# DigitalIO.net
KiCad netlist of a schematic drawn in Altium Designer
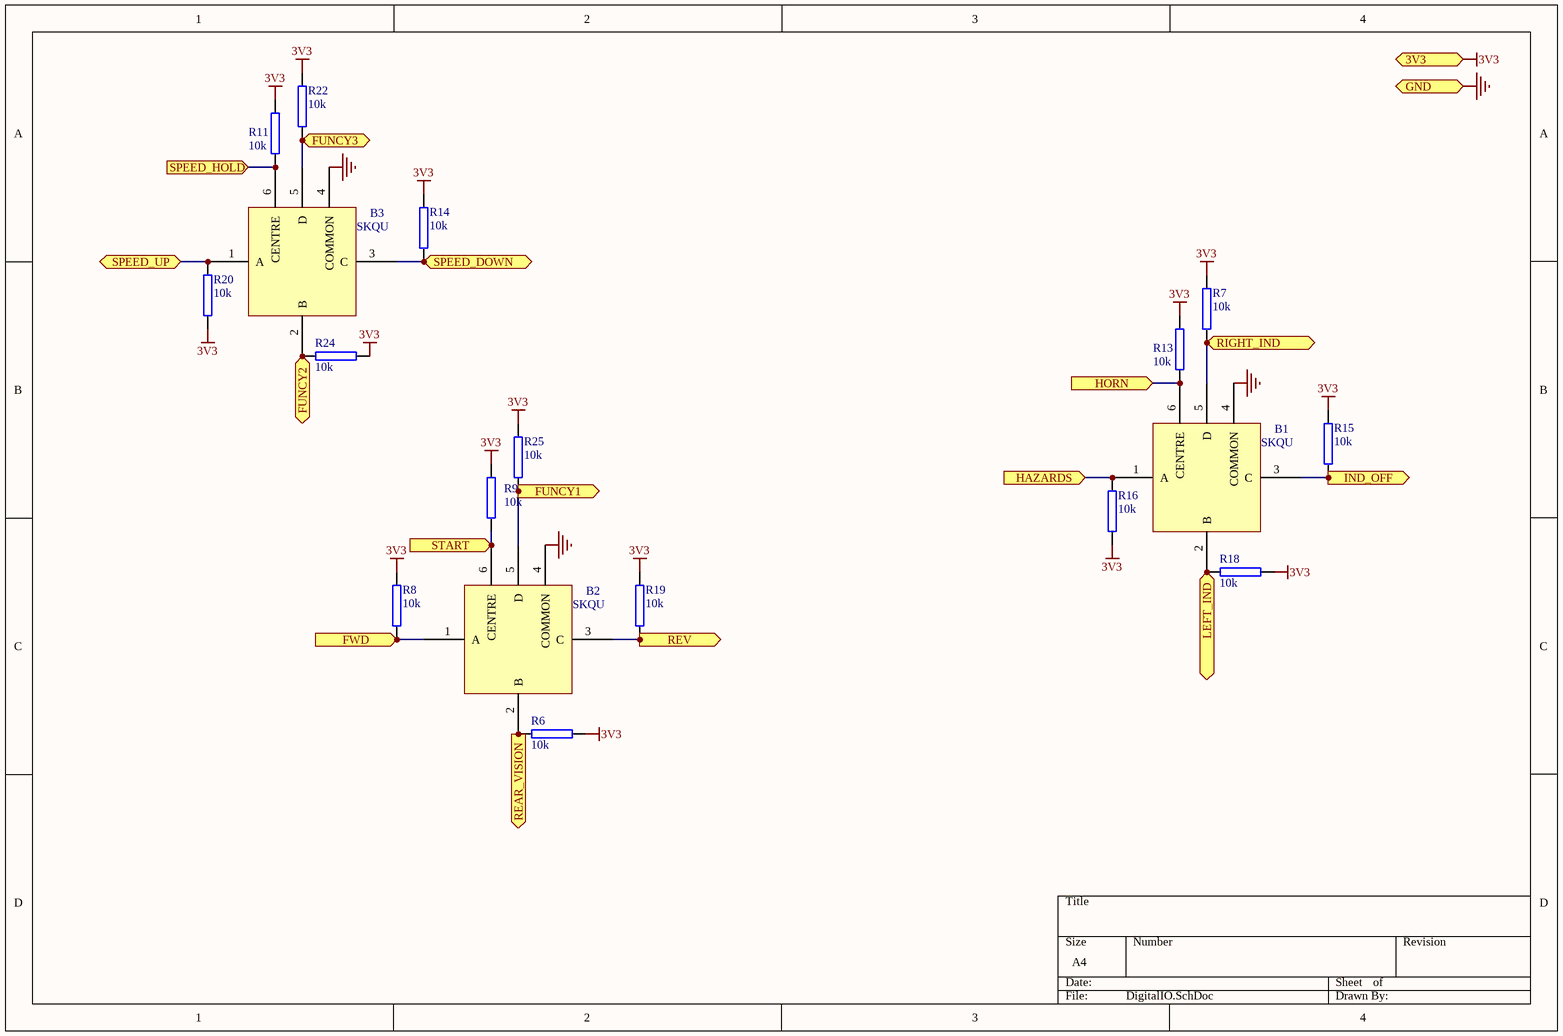
[diagram p0: DigitalIO.SchDoc]

(export (version "E")
  (design (tool "Eeschema 10.0.6"))
  (components
    (comp (ref "B1")
      (value "SKQU")
      (footprint "SKQU")
      (description "Multi-directional switch")
      (libsource (lib "Miscellaneous") (part "SKQU"))
    )
    (comp (ref "B2")
      (value "SKQU")
      (footprint "SKQU")
      (description "Multi-directional switch")
      (libsource (lib "Miscellaneous") (part "SKQU"))
    )
    (comp (ref "B3")
      (value "SKQU")
      (footprint "SKQU")
      (description "Multi-directional switch")
      (libsource (lib "Miscellaneous") (part "SKQU"))
    )
    (comp (ref "R6")
      (value "10k")
      (footprint "0603")
      (description "Standard Resistor")
      (libsource (lib "*") (part "RES"))
    )
    (comp (ref "R7")
      (value "10k")
      (footprint "0603")
      (description "Standard Resistor")
      (libsource (lib "*") (part "RES"))
    )
    (comp (ref "R8")
      (value "10k")
      (footprint "0603")
      (description "Standard Resistor")
      (libsource (lib "*") (part "RES"))
    )
    (comp (ref "R9")
      (value "10k")
      (footprint "0603")
      (description "Standard Resistor")
      (libsource (lib "*") (part "RES"))
    )
    (comp (ref "R11")
      (value "10k")
      (footprint "0603")
      (description "Standard Resistor")
      (libsource (lib "*") (part "RES"))
    )
    (comp (ref "R13")
      (value "10k")
      (footprint "0603")
      (description "Standard Resistor")
      (libsource (lib "*") (part "RES"))
    )
    (comp (ref "R14")
      (value "10k")
      (footprint "0603")
      (description "Standard Resistor")
      (libsource (lib "*") (part "RES"))
    )
    (comp (ref "R15")
      (value "10k")
      (footprint "0603")
      (description "Standard Resistor")
      (libsource (lib "*") (part "RES"))
    )
    (comp (ref "R16")
      (value "10k")
      (footprint "0603")
      (description "Standard Resistor")
      (libsource (lib "*") (part "RES"))
    )
    (comp (ref "R18")
      (value "10k")
      (footprint "0603")
      (description "Standard Resistor")
      (libsource (lib "*") (part "RES"))
    )
    (comp (ref "R19")
      (value "10k")
      (footprint "0603")
      (description "Standard Resistor")
      (libsource (lib "*") (part "RES"))
    )
    (comp (ref "R20")
      (value "10k")
      (footprint "0603")
      (description "Standard Resistor")
      (libsource (lib "*") (part "RES"))
    )
    (comp (ref "R22")
      (value "10k")
      (footprint "0603")
      (description "Standard Resistor")
      (libsource (lib "*") (part "RES"))
    )
    (comp (ref "R24")
      (value "10k")
      (footprint "0603")
      (description "Standard Resistor")
      (libsource (lib "*") (part "RES"))
    )
    (comp (ref "R25")
      (value "10k")
      (footprint "0603")
      (description "Standard Resistor")
      (libsource (lib "*") (part "RES"))
    )
  )
  (nets
    (net (code "1") (name "/FUNCY1") (class "Default")
      (node (ref "B2") (pin "5") (pinfunction "D_5") (pintype "passive"))
      (node (ref "R25") (pin "2") (pintype "passive"))
    )
    (net (code "2") (name "/FUNCY2") (class "Default")
      (node (ref "B3") (pin "2") (pinfunction "B_2") (pintype "passive"))
      (node (ref "R24") (pin "1") (pintype "passive"))
    )
    (net (code "3") (name "/FUNCY3") (class "Default")
      (node (ref "B3") (pin "5") (pinfunction "D_5") (pintype "passive"))
      (node (ref "R22") (pin "2") (pintype "passive"))
    )
    (net (code "4") (name "/FWD") (class "Default")
      (node (ref "B2") (pin "1") (pinfunction "A_1") (pintype "passive"))
      (node (ref "R8") (pin "1") (pintype "passive"))
    )
    (net (code "5") (name "/HAZARDS") (class "Default")
      (node (ref "B1") (pin "1") (pinfunction "A_1") (pintype "passive"))
      (node (ref "R16") (pin "2") (pintype "passive"))
    )
    (net (code "6") (name "/HORN") (class "Default")
      (node (ref "B1") (pin "6") (pinfunction "CENTRE_6") (pintype "passive"))
      (node (ref "R13") (pin "2") (pintype "passive"))
    )
    (net (code "7") (name "/IND_OFF") (class "Default")
      (node (ref "B1") (pin "3") (pinfunction "C_3") (pintype "passive"))
      (node (ref "R15") (pin "2") (pintype "passive"))
    )
    (net (code "8") (name "/LEFT_IND") (class "Default")
      (node (ref "B1") (pin "2") (pinfunction "B_2") (pintype "passive"))
      (node (ref "R18") (pin "2") (pintype "passive"))
    )
    (net (code "9") (name "/REAR_VISION") (class "Default")
      (node (ref "B2") (pin "2") (pinfunction "B_2") (pintype "passive"))
      (node (ref "R6") (pin "2") (pintype "passive"))
    )
    (net (code "10") (name "/REV") (class "Default")
      (node (ref "B2") (pin "3") (pinfunction "C_3") (pintype "passive"))
      (node (ref "R19") (pin "2") (pintype "passive"))
    )
    (net (code "11") (name "/RIGHT_IND") (class "Default")
      (node (ref "B1") (pin "5") (pinfunction "D_5") (pintype "passive"))
      (node (ref "R7") (pin "2") (pintype "passive"))
    )
    (net (code "12") (name "/SPEED_DOWN") (class "Default")
      (node (ref "B3") (pin "3") (pinfunction "C_3") (pintype "passive"))
      (node (ref "R14") (pin "2") (pintype "passive"))
    )
    (net (code "13") (name "/SPEED_HOLD") (class "Default")
      (node (ref "B3") (pin "6") (pinfunction "CENTRE_6") (pintype "passive"))
      (node (ref "R11") (pin "2") (pintype "passive"))
    )
    (net (code "14") (name "/SPEED_UP") (class "Default")
      (node (ref "B3") (pin "1") (pinfunction "A_1") (pintype "passive"))
      (node (ref "R20") (pin "2") (pintype "passive"))
    )
    (net (code "15") (name "/START") (class "Default")
      (node (ref "B2") (pin "6") (pinfunction "CENTRE_6") (pintype "passive"))
      (node (ref "R9") (pin "2") (pintype "passive"))
    )
    (net (code "16") (name "3V3") (class "Default")
      (node (ref "R11") (pin "1") (pintype "passive"))
      (node (ref "R13") (pin "1") (pintype "passive"))
      (node (ref "R14") (pin "1") (pintype "passive"))
      (node (ref "R15") (pin "1") (pintype "passive"))
      (node (ref "R16") (pin "1") (pintype "passive"))
      (node (ref "R18") (pin "1") (pintype "passive"))
      (node (ref "R19") (pin "1") (pintype "passive"))
      (node (ref "R20") (pin "1") (pintype "passive"))
      (node (ref "R22") (pin "1") (pintype "passive"))
      (node (ref "R24") (pin "2") (pintype "passive"))
      (node (ref "R25") (pin "1") (pintype "passive"))
      (node (ref "R6") (pin "1") (pintype "passive"))
      (node (ref "R7") (pin "1") (pintype "passive"))
      (node (ref "R8") (pin "2") (pintype "passive"))
      (node (ref "R9") (pin "1") (pintype "passive"))
    )
    (net (code "17") (name "GND") (class "Default")
      (node (ref "B1") (pin "4") (pinfunction "COMMON_4") (pintype "passive"))
      (node (ref "B2") (pin "4") (pinfunction "COMMON_4") (pintype "passive"))
      (node (ref "B3") (pin "4") (pinfunction "COMMON_4") (pintype "passive"))
    )
  )
)
